# supply.net
KiCad netlist of a schematic drawn in Altium Designer
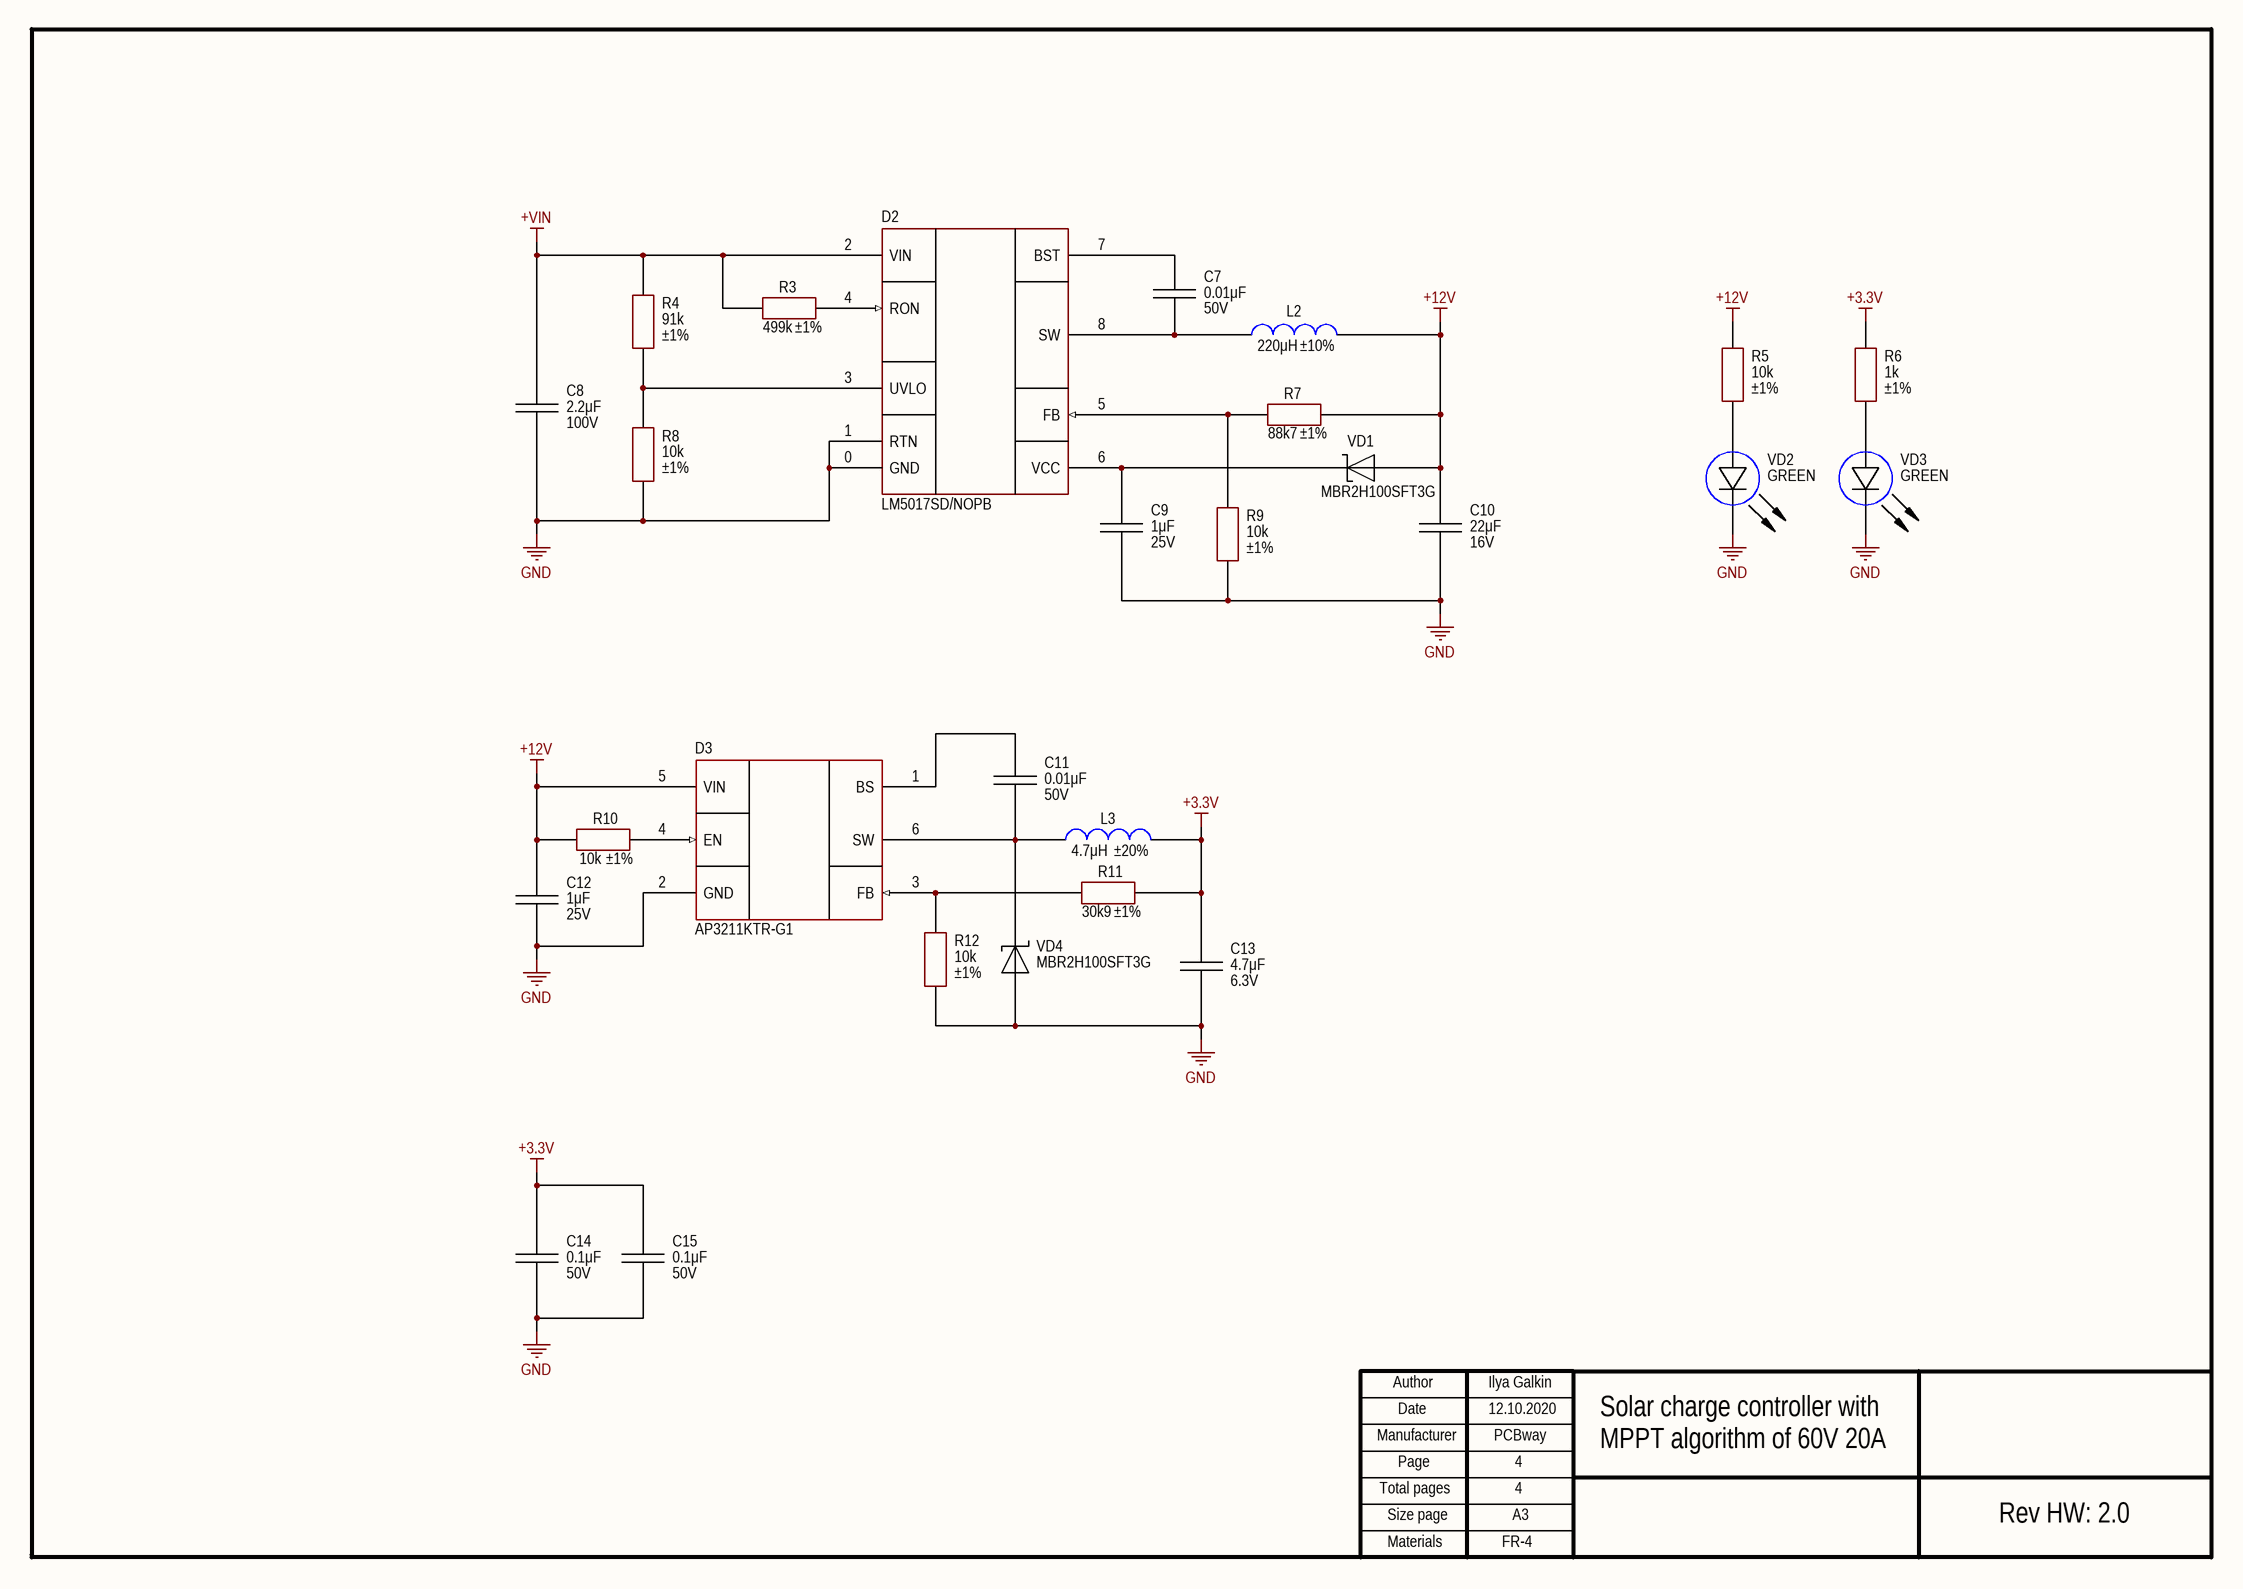
[diagram p0: supply.SchDoc]

(export (version "E")
  (design (tool "Eeschema 10.0.6"))
  (components
    (comp (ref "C7")
      (value "0.01μF")
      (footprint "CAP: 0603")
      (fields
        (field (name "MANUFACTURER") "Samsung")
        (field (name "PARTNUMBER") "CL10B103KB8NNNC")
        (field (name "VALUEMANUFACTURERPARTNUMBER") "Ceramic capacitor, 0.01μF, X7R, ±10%, 50V, 0603, -55...+125°C")
        (field (name "VOLTAGE") "50V")
      )
      (libsource (lib "Capacitor") (part "Ceramic_0603"))
    )
    (comp (ref "C8")
      (value "2.2μF")
      (footprint "CAP: 1210")
      (fields
        (field (name "MANUFACTURER") "Samsung")
        (field (name "PARTNUMBER") "CL32B225KCJSNNE")
        (field (name "VALUEMANUFACTURERPARTNUMBER") "Ceramic capacitor, 2.2μF, X7R, ±10%, 100V, 1210, -55...+125°C")
        (field (name "VOLTAGE") "100V")
      )
      (libsource (lib "capacitor") (part "Ceramic_1210"))
    )
    (comp (ref "C9")
      (value "1μF")
      (footprint "CAP: 0603")
      (fields
        (field (name "MANUFACTURER") "Samsung")
        (field (name "PARTNUMBER") "CL10B105KA8NNNC")
        (field (name "VALUEMANUFACTURERPARTNUMBER") "Ceramic capacitor, 1μF, X7R, ±10%, 25V, 0603, -55...+125°C")
        (field (name "VOLTAGE") "25V")
      )
      (libsource (lib "Capacitor") (part "Ceramic_0603"))
    )
    (comp (ref "C10")
      (value "22μF")
      (footprint "CAP: 1210")
      (fields
        (field (name "MANUFACTURER") "Samsung")
        (field (name "PARTNUMBER") "CL32B226KOJNNNE")
        (field (name "VALUEMANUFACTURERPARTNUMBER") "Ceramic capacitor, 22μF, X7R, ±10%, 16V, 1210, -55...+125°C")
        (field (name "VOLTAGE") "16V")
      )
      (libsource (lib "capacitor") (part "Ceramic_1210"))
    )
    (comp (ref "C11")
      (value "0.01μF")
      (footprint "CAP: 0603")
      (fields
        (field (name "MANUFACTURER") "Samsung")
        (field (name "PARTNUMBER") "CL10B103KB8NNNC")
        (field (name "VALUEMANUFACTURERPARTNUMBER") "Ceramic capacitor, 0.01μF, X7R, ±10%, 50V, 0603, -55...+125°C")
        (field (name "VOLTAGE") "50V")
      )
      (libsource (lib "Capacitor") (part "Ceramic_0603"))
    )
    (comp (ref "C12")
      (value "1μF")
      (footprint "CAP: 0603")
      (fields
        (field (name "MANUFACTURER") "Samsung")
        (field (name "PARTNUMBER") "CL10B105KA8NNNC")
        (field (name "VALUEMANUFACTURERPARTNUMBER") "Ceramic capacitor, 1μF, X7R, ±10%, 25V, 0603, -55...+125°C")
        (field (name "VOLTAGE") "25V")
      )
      (libsource (lib "Capacitor") (part "Ceramic_0603"))
    )
    (comp (ref "C13")
      (value "4.7μF")
      (footprint "CAP: 0603")
      (fields
        (field (name "MANUFACTURER") "Samsung")
        (field (name "PARTNUMBER") "CL10B475KQ8NQNC")
        (field (name "VALUEMANUFACTURERPARTNUMBER") "Ceramic capacitor, 4.7μF, X7R, ±10%, 6.3V, 0603, -55...+125°C")
        (field (name "VOLTAGE") "6.3V")
      )
      (libsource (lib "Capacitor") (part "Ceramic_0603"))
    )
    (comp (ref "C14")
      (value "0.1μF")
      (footprint "CAP: 0603")
      (fields
        (field (name "MANUFACTURER") "Samsung")
        (field (name "PARTNUMBER") "CL10B104KB8WPND")
        (field (name "VALUEMANUFACTURERPARTNUMBER") "Ceramic capacitor, 0.1μF, X7R, ±10%, 50V, 0603, -55...+125°C")
        (field (name "VOLTAGE") "50V")
      )
      (libsource (lib "Capacitor") (part "Ceramic_0603"))
    )
    (comp (ref "C15")
      (value "0.1μF")
      (footprint "CAP: 0603")
      (fields
        (field (name "MANUFACTURER") "Samsung")
        (field (name "PARTNUMBER") "CL10B104KB8WPND")
        (field (name "VALUEMANUFACTURERPARTNUMBER") "Ceramic capacitor, 0.1μF, X7R, ±10%, 50V, 0603, -55...+125°C")
        (field (name "VOLTAGE") "50V")
      )
      (libsource (lib "Capacitor") (part "Ceramic_0603"))
    )
    (comp (ref "D2")
      (value "~")
      (footprint "8-WSON (4x4)")
      (description "Buck converter")
      (fields
        (field (name "MANUFACTURER") "Texas Instruments")
        (field (name "VALUEMANUFACTURERPARTNUMBER") "DC/DC buck converter, input 7.5...100V, 1MHz, output 1.225...90V, 0.6A, -40...+125°C, 8-WSON")
        (field (name "PARTNUMBER") "LM5017SD/NOPB")
      )
      (libsource (lib "ic-power-supply") (part "LM5017SD"))
    )
    (comp (ref "D3")
      (value "~")
      (footprint "SOT23-6")
      (description "Buck converter")
      (fields
        (field (name "MANUFACTURER") "Diodes Incorporated")
        (field (name "VALUEMANUFACTURERPARTNUMBER") "DC/DC buck converter, input 4.5...18V, 1.4MHz, output 0.81...15V, 1.5A, -40...+85°C, SOT23-6")
        (field (name "PARTNUMBER") "AP3211KTR-G1")
      )
      (libsource (lib "ic-power-supply") (part "AP3211KTR-G1"))
    )
    (comp (ref "L2")
      (value "220μH")
      (footprint "IND: SDR0805")
      (fields
        (field (name "MANUFACTURER") "Bourns")
        (field (name "PARTNUMBER") "SDR0805-221KL")
        (field (name "VALUEMANUFACTURERPARTNUMBER") "Fixed inductor, 220μH, ±10%, SDR0805, 490mA, -40...+125°C")
        (field (name "TOLERANCE") "±10%")
      )
      (libsource (lib "Inductor") (part "Inductor_SDR0805"))
    )
    (comp (ref "L3")
      (value "4.7μH")
      (footprint "IND: CD32")
      (fields
        (field (name "MANUFACTURER") "YJYCOIN")
        (field (name "PARTNUMBER") "CD32YP0302-4R7M")
        (field (name "VALUEMANUFACTURERPARTNUMBER") "Fixed inductor, 4.7μH, ±20%, CD32 series, 1.5A, -40...+125°C")
        (field (name "TOLERANCE") "±20%")
      )
      (libsource (lib "inductor") (part "Inductor_CD32"))
    )
    (comp (ref "R3")
      (value "499k")
      (footprint "RES: 0603")
      (fields
        (field (name "MANUFACTURER") "Yageo")
        (field (name "PARTNUMBER") "RC0603FR-07499KL")
        (field (name "VALUEMANUFACTURERPARTNUMBER") "Resistor film, 499k, ±1%, 0603, 0.1W, -55...+125°C")
        (field (name "TOLERANCE") "±1%")
      )
      (libsource (lib "Resistor") (part "Resistor_0603"))
    )
    (comp (ref "R4")
      (value "91k")
      (footprint "RES: 0603")
      (fields
        (field (name "MANUFACTURER") "Yageo")
        (field (name "PARTNUMBER") "RC0603FR-0791KL")
        (field (name "VALUEMANUFACTURERPARTNUMBER") "Resistor film, 91k, ±1%, 0603, 0.1W, -55...+125°C")
        (field (name "TOLERANCE") "±1%")
      )
      (libsource (lib "") (part "Resistor_0603_1"))
    )
    (comp (ref "R5")
      (value "10k")
      (footprint "RES: 0603")
      (fields
        (field (name "MANUFACTURER") "Yageo")
        (field (name "PARTNUMBER") "AC0603FR-0710KL")
        (field (name "VALUEMANUFACTURERPARTNUMBER") "Resistor film, 10k, ±1%, 0603, 0.1W, -55...+125°C")
        (field (name "TOLERANCE") "±1%")
      )
      (libsource (lib "") (part "Resistor_0603_1"))
    )
    (comp (ref "R6")
      (value "1k")
      (footprint "RES: 0603")
      (fields
        (field (name "MANUFACTURER") "Yageo")
        (field (name "PARTNUMBER") "RC0603FR-071KL")
        (field (name "VALUEMANUFACTURERPARTNUMBER") "Resistor film, 1k, ±1%, 0603, 0.1W, -55...+125°C")
        (field (name "TOLERANCE") "±1%")
      )
      (libsource (lib "") (part "Resistor_0603_1"))
    )
    (comp (ref "R7")
      (value "88k7")
      (footprint "RES: 0603")
      (fields
        (field (name "MANUFACTURER") "Yageo")
        (field (name "PARTNUMBER") "RC0603FR-0788K7L")
        (field (name "VALUEMANUFACTURERPARTNUMBER") "Resistor film, 88k7, ±1%, 0603, 0.1W, -55...+125°C")
        (field (name "TOLERANCE") "±1%")
      )
      (libsource (lib "Resistor") (part "Resistor_0603"))
    )
    (comp (ref "R8")
      (value "10k")
      (footprint "RES: 0603")
      (fields
        (field (name "MANUFACTURER") "Yageo")
        (field (name "PARTNUMBER") "AC0603FR-0710KL")
        (field (name "VALUEMANUFACTURERPARTNUMBER") "Resistor film, 10k, ±1%, 0603, 0.1W, -55...+125°C")
        (field (name "TOLERANCE") "±1%")
      )
      (libsource (lib "") (part "Resistor_0603_1"))
    )
    (comp (ref "R9")
      (value "10k")
      (footprint "RES: 0603")
      (fields
        (field (name "MANUFACTURER") "Yageo")
        (field (name "PARTNUMBER") "AC0603FR-0710KL")
        (field (name "VALUEMANUFACTURERPARTNUMBER") "Resistor film, 10k, ±1%, 0603, 0.1W, -55...+125°C")
        (field (name "TOLERANCE") "±1%")
      )
      (libsource (lib "") (part "Resistor_0603_1"))
    )
    (comp (ref "R10")
      (value "10k")
      (footprint "RES: 0603")
      (fields
        (field (name "MANUFACTURER") "Yageo")
        (field (name "PARTNUMBER") "AC0603FR-0710KL")
        (field (name "VALUEMANUFACTURERPARTNUMBER") "Resistor film, 10k, ±1%, 0603, 0.1W, -55...+125°C")
        (field (name "TOLERANCE") "±1%")
      )
      (libsource (lib "Resistor") (part "Resistor_0603"))
    )
    (comp (ref "R11")
      (value "30k9")
      (footprint "RES: 0603")
      (fields
        (field (name "MANUFACTURER") "Yageo")
        (field (name "PARTNUMBER") "RC0603FR-0730K9L")
        (field (name "VALUEMANUFACTURERPARTNUMBER") "Resistor film, 30k9, ±1%, 0603, 0.1W, -55...+125°C")
        (field (name "TOLERANCE") "±1%")
      )
      (libsource (lib "Resistor") (part "Resistor_0603"))
    )
    (comp (ref "R12")
      (value "10k")
      (footprint "RES: 0603")
      (fields
        (field (name "MANUFACTURER") "Yageo")
        (field (name "PARTNUMBER") "AC0603FR-0710KL")
        (field (name "VALUEMANUFACTURERPARTNUMBER") "Resistor film, 10k, ±1%, 0603, 0.1W, -55...+125°C")
        (field (name "TOLERANCE") "±1%")
      )
      (libsource (lib "") (part "Resistor_0603_1"))
    )
    (comp (ref "VD1")
      (value "~")
      (footprint "DIODE: SOD123F")
      (fields
        (field (name "MANUFACTURER") "ON Semiconductor")
        (field (name "VALUEMANUFACTURERPARTNUMBER") "Schottky diode, 100V, 2A, 840mV, 15pF, SOD-123F, -55...+150°C")
        (field (name "VOLTAGE") "100V")
        (field (name "PARTNUMBER") "MBR2H100SFT3G")
      )
      (libsource (lib "Diode") (part "Schottky_single"))
    )
    (comp (ref "VD2")
      (value "~")
      (footprint "LED: 0603G")
      (fields
        (field (name "MANUFACTURER") "Wurth")
        (field (name "VALUEMANUFACTURERPARTNUMBER") "LED, 20mA, 2V, 0603, -55...+150°C")
        (field (name "PARTNUMBER") "150060VS75000")
        (field (name "COLOR") "GREEN")
      )
      (libsource (lib "Diode") (part "LED_single"))
    )
    (comp (ref "VD3")
      (value "~")
      (footprint "LED: 0603G")
      (fields
        (field (name "MANUFACTURER") "Wurth")
        (field (name "VALUEMANUFACTURERPARTNUMBER") "LED, 20mA, 2V, 0603, -55...+150°C")
        (field (name "PARTNUMBER") "150060VS75000")
        (field (name "COLOR") "GREEN")
      )
      (libsource (lib "Diode") (part "LED_single"))
    )
    (comp (ref "VD4")
      (value "~")
      (footprint "DIODE: SOD123F")
      (fields
        (field (name "MANUFACTURER") "ON Semiconductor")
        (field (name "VALUEMANUFACTURERPARTNUMBER") "Schottky diode, 100V, 2A, 840mV, 15pF, SOD-123F, -55...+150°C")
        (field (name "VOLTAGE") "100V")
        (field (name "PARTNUMBER") "MBR2H100SFT3G")
      )
      (libsource (lib "Diode") (part "Schottky_single"))
    )
  )
  (nets
    (net (code "1") (name "+3.3V") (class "Default")
      (node (ref "C13") (pin "2") (pinfunction "2_2") (pintype "power_in"))
      (node (ref "C14") (pin "2") (pinfunction "2_2") (pintype "power_in"))
      (node (ref "C15") (pin "2") (pinfunction "2_2") (pintype "power_in"))
      (node (ref "L3") (pin "1") (pinfunction "1_1") (pintype "passive"))
      (node (ref "R11") (pin "1") (pinfunction "1_1") (pintype "passive"))
      (node (ref "R6") (pin "2") (pinfunction "2_2") (pintype "passive"))
    )
    (net (code "2") (name "+12V") (class "Default")
      (node (ref "C10") (pin "2") (pinfunction "2_2") (pintype "passive"))
      (node (ref "C12") (pin "2") (pinfunction "2_2") (pintype "power_in"))
      (node (ref "D3") (pin "5") (pinfunction "VIN_5") (pintype "passive"))
      (node (ref "L2") (pin "1") (pinfunction "1_1") (pintype "passive"))
      (node (ref "R10") (pin "2") (pinfunction "2_2") (pintype "passive"))
      (node (ref "R5") (pin "2") (pinfunction "2_2") (pintype "passive"))
      (node (ref "R7") (pin "1") (pinfunction "1_1") (pintype "passive"))
      (node (ref "VD1") (pin "1") (pinfunction "1_1") (pintype "passive"))
    )
    (net (code "3") (name "+VIN") (class "Default")
      (node (ref "C8") (pin "2") (pinfunction "2_2") (pintype "passive"))
      (node (ref "D2") (pin "2") (pinfunction "VIN_2") (pintype "passive"))
      (node (ref "R3") (pin "2") (pinfunction "2_2") (pintype "passive"))
      (node (ref "R4") (pin "2") (pinfunction "2_2") (pintype "passive"))
    )
    (net (code "4") (name "GND") (class "Default")
      (node (ref "C10") (pin "1") (pinfunction "1_1") (pintype "passive"))
      (node (ref "C12") (pin "1") (pinfunction "1_1") (pintype "power_in"))
      (node (ref "C13") (pin "1") (pinfunction "1_1") (pintype "power_in"))
      (node (ref "C14") (pin "1") (pinfunction "1_1") (pintype "power_in"))
      (node (ref "C15") (pin "1") (pinfunction "1_1") (pintype "power_in"))
      (node (ref "C8") (pin "1") (pinfunction "1_1") (pintype "passive"))
      (node (ref "C9") (pin "1") (pinfunction "1_1") (pintype "power_in"))
      (node (ref "D2") (pin "0") (pinfunction "GND_0") (pintype "passive"))
      (node (ref "D2") (pin "1") (pinfunction "RTN_1") (pintype "passive"))
      (node (ref "D3") (pin "2") (pinfunction "GND_2") (pintype "passive"))
      (node (ref "R12") (pin "1") (pinfunction "1_1") (pintype "passive"))
      (node (ref "R8") (pin "1") (pinfunction "1_1") (pintype "passive"))
      (node (ref "R9") (pin "1") (pinfunction "1_1") (pintype "passive"))
      (node (ref "VD2") (pin "2") (pinfunction "C_2") (pintype "passive"))
      (node (ref "VD3") (pin "2") (pinfunction "C_2") (pintype "passive"))
      (node (ref "VD4") (pin "1") (pinfunction "1_1") (pintype "passive"))
    )
    (net (code "5") (name "Net-(D2-BST)") (class "Default")
      (node (ref "C7") (pin "2") (pinfunction "2_2") (pintype "power_in"))
      (node (ref "D2") (pin "7") (pinfunction "BST_7") (pintype "passive"))
    )
    (net (code "6") (name "Net-(D2-FB)") (class "Default")
      (node (ref "D2") (pin "5") (pinfunction "FB_5") (pintype "input"))
      (node (ref "R7") (pin "2") (pinfunction "2_2") (pintype "passive"))
      (node (ref "R9") (pin "2") (pinfunction "2_2") (pintype "passive"))
    )
    (net (code "7") (name "Net-(D2-RON)") (class "Default")
      (node (ref "D2") (pin "4") (pinfunction "RON_4") (pintype "input"))
      (node (ref "R3") (pin "1") (pinfunction "1_1") (pintype "passive"))
    )
    (net (code "8") (name "Net-(D2-SW)") (class "Default")
      (node (ref "C7") (pin "1") (pinfunction "1_1") (pintype "power_in"))
      (node (ref "D2") (pin "8") (pinfunction "SW_8") (pintype "passive"))
      (node (ref "L2") (pin "2") (pinfunction "2_2") (pintype "passive"))
    )
    (net (code "9") (name "Net-(D2-UVLO)") (class "Default")
      (node (ref "D2") (pin "3") (pinfunction "UVLO_3") (pintype "passive"))
      (node (ref "R4") (pin "1") (pinfunction "1_1") (pintype "passive"))
      (node (ref "R8") (pin "2") (pinfunction "2_2") (pintype "passive"))
    )
    (net (code "10") (name "Net-(D2-VCC)") (class "Default")
      (node (ref "C9") (pin "2") (pinfunction "2_2") (pintype "power_in"))
      (node (ref "D2") (pin "6") (pinfunction "VCC_6") (pintype "passive"))
      (node (ref "VD1") (pin "2") (pinfunction "2_2") (pintype "passive"))
    )
    (net (code "11") (name "Net-(D3-BS)") (class "Default")
      (node (ref "C11") (pin "2") (pinfunction "2_2") (pintype "power_in"))
      (node (ref "D3") (pin "1") (pinfunction "BS_1") (pintype "passive"))
    )
    (net (code "12") (name "Net-(D3-EN)") (class "Default")
      (node (ref "D3") (pin "4") (pinfunction "EN_4") (pintype "input"))
      (node (ref "R10") (pin "1") (pinfunction "1_1") (pintype "passive"))
    )
    (net (code "13") (name "Net-(D3-FB)") (class "Default")
      (node (ref "D3") (pin "3") (pinfunction "FB_3") (pintype "input"))
      (node (ref "R11") (pin "2") (pinfunction "2_2") (pintype "passive"))
      (node (ref "R12") (pin "2") (pinfunction "2_2") (pintype "passive"))
    )
    (net (code "14") (name "Net-(D3-SW)") (class "Default")
      (node (ref "C11") (pin "1") (pinfunction "1_1") (pintype "power_in"))
      (node (ref "D3") (pin "6") (pinfunction "SW_6") (pintype "passive"))
      (node (ref "L3") (pin "2") (pinfunction "2_2") (pintype "passive"))
      (node (ref "VD4") (pin "2") (pinfunction "2_2") (pintype "passive"))
    )
    (net (code "15") (name "Net-(VD2-A)") (class "Default")
      (node (ref "R5") (pin "1") (pinfunction "1_1") (pintype "passive"))
      (node (ref "VD2") (pin "1") (pinfunction "A_1") (pintype "passive"))
    )
    (net (code "16") (name "Net-(VD3-A)") (class "Default")
      (node (ref "R6") (pin "1") (pinfunction "1_1") (pintype "passive"))
      (node (ref "VD3") (pin "1") (pinfunction "A_1") (pintype "passive"))
    )
  )
)
